# pc-gen-breadboard.net
KiCad netlist of a schematic drawn in EAGLE
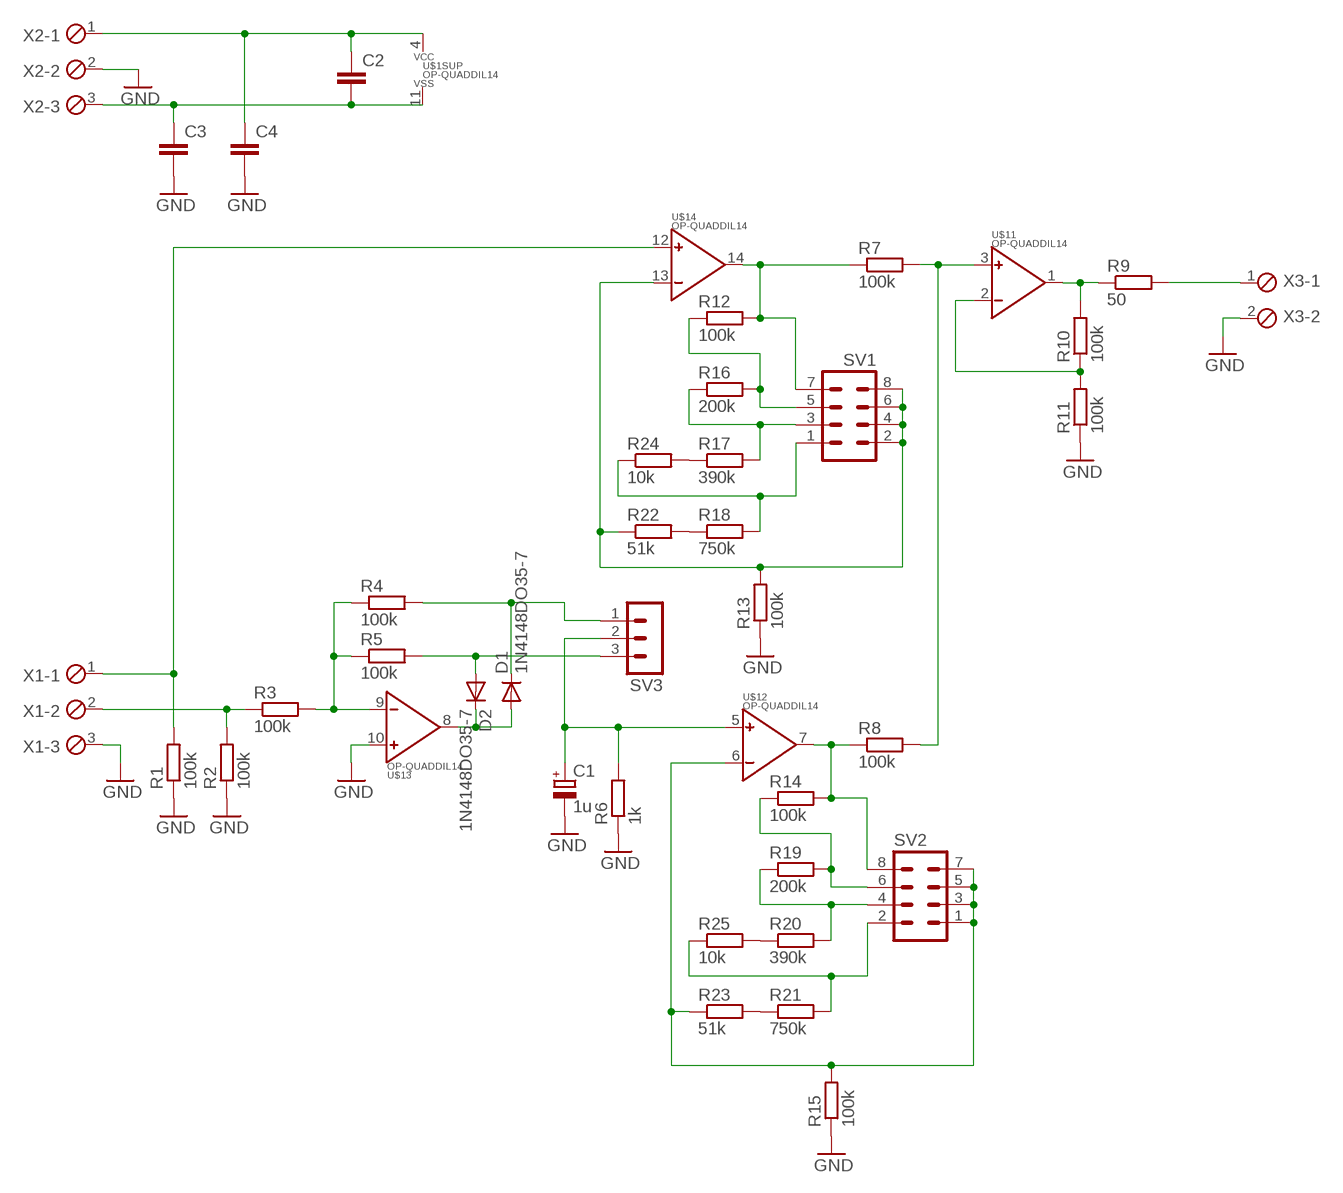
[diagram p0: schematic, sheet 1]

(export (version "E")
  (design (tool "Eeschema 10.0.6"))
  (components
    (comp (ref "C1")
      (value "1u")
      (footprint "eagle-import:E2,5-7")
      (libsource (lib "eagle-import") (part "CPOL-EUE2.5-7"))
    )
    (comp (ref "C2")
      (value "C-EU050-025X075")
      (footprint "eagle-import:C050-025X075")
      (libsource (lib "eagle-import") (part "C-EU050-025X075"))
    )
    (comp (ref "C3")
      (value "C-EU050-025X075")
      (footprint "eagle-import:C050-025X075")
      (libsource (lib "eagle-import") (part "C-EU050-025X075"))
    )
    (comp (ref "C4")
      (value "C-EU050-025X075")
      (footprint "eagle-import:C050-025X075")
      (libsource (lib "eagle-import") (part "C-EU050-025X075"))
    )
    (comp (ref "D1")
      (value "1N4148DO35-7")
      (footprint "eagle-import:DO35-7")
      (libsource (lib "eagle-import") (part "1N4148DO35-7"))
    )
    (comp (ref "D2")
      (value "1N4148DO35-7")
      (footprint "eagle-import:DO35-7")
      (libsource (lib "eagle-import") (part "1N4148DO35-7"))
    )
    (comp (ref "R1")
      (value "100k")
      (footprint "eagle-import:0207_2V")
      (libsource (lib "eagle-import") (part "R-EU_0207/2V"))
    )
    (comp (ref "R2")
      (value "100k")
      (footprint "eagle-import:0207_2V")
      (libsource (lib "eagle-import") (part "R-EU_0207/2V"))
    )
    (comp (ref "R3")
      (value "100k")
      (footprint "eagle-import:0207_7")
      (libsource (lib "eagle-import") (part "R-EU_0207/7"))
    )
    (comp (ref "R4")
      (value "100k")
      (footprint "eagle-import:0207_2V")
      (libsource (lib "eagle-import") (part "R-EU_0207/2V"))
    )
    (comp (ref "R5")
      (value "100k")
      (footprint "eagle-import:0207_2V")
      (libsource (lib "eagle-import") (part "R-EU_0207/2V"))
    )
    (comp (ref "R6")
      (value "1k")
      (footprint "eagle-import:0207_2V")
      (libsource (lib "eagle-import") (part "R-EU_0207/2V"))
    )
    (comp (ref "R7")
      (value "100k")
      (footprint "eagle-import:0207_7")
      (libsource (lib "eagle-import") (part "R-EU_0207/7"))
    )
    (comp (ref "R8")
      (value "100k")
      (footprint "eagle-import:0207_7")
      (libsource (lib "eagle-import") (part "R-EU_0207/7"))
    )
    (comp (ref "R9")
      (value "50")
      (footprint "eagle-import:0207_7")
      (libsource (lib "eagle-import") (part "R-EU_0207/7"))
    )
    (comp (ref "R10")
      (value "100k")
      (footprint "eagle-import:0207_2V")
      (libsource (lib "eagle-import") (part "R-EU_0207/2V"))
    )
    (comp (ref "R11")
      (value "100k")
      (footprint "eagle-import:0207_7")
      (libsource (lib "eagle-import") (part "R-EU_0207/7"))
    )
    (comp (ref "R12")
      (value "100k")
      (footprint "eagle-import:0207_2V")
      (libsource (lib "eagle-import") (part "R-EU_0207/2V"))
    )
    (comp (ref "R13")
      (value "100k")
      (footprint "eagle-import:0207_7")
      (libsource (lib "eagle-import") (part "R-EU_0207/7"))
    )
    (comp (ref "R14")
      (value "100k")
      (footprint "eagle-import:0207_2V")
      (libsource (lib "eagle-import") (part "R-EU_0207/2V"))
    )
    (comp (ref "R15")
      (value "100k")
      (footprint "eagle-import:0207_2V")
      (libsource (lib "eagle-import") (part "R-EU_0207/2V"))
    )
    (comp (ref "R16")
      (value "200k")
      (footprint "eagle-import:0207_2V")
      (libsource (lib "eagle-import") (part "R-EU_0207/2V"))
    )
    (comp (ref "R17")
      (value "390k")
      (footprint "eagle-import:0207_2V")
      (libsource (lib "eagle-import") (part "R-EU_0207/2V"))
    )
    (comp (ref "R18")
      (value "750k")
      (footprint "eagle-import:0207_2V")
      (libsource (lib "eagle-import") (part "R-EU_0207/2V"))
    )
    (comp (ref "R19")
      (value "200k")
      (footprint "eagle-import:0207_2V")
      (libsource (lib "eagle-import") (part "R-EU_0207/2V"))
    )
    (comp (ref "R20")
      (value "390k")
      (footprint "eagle-import:0207_2V")
      (libsource (lib "eagle-import") (part "R-EU_0207/2V"))
    )
    (comp (ref "R21")
      (value "750k")
      (footprint "eagle-import:0207_2V")
      (libsource (lib "eagle-import") (part "R-EU_0207/2V"))
    )
    (comp (ref "R22")
      (value "51k")
      (footprint "eagle-import:0207_2V")
      (libsource (lib "eagle-import") (part "R-EU_0207/2V"))
    )
    (comp (ref "R23")
      (value "51k")
      (footprint "eagle-import:0207_2V")
      (libsource (lib "eagle-import") (part "R-EU_0207/2V"))
    )
    (comp (ref "R24")
      (value "10k")
      (footprint "eagle-import:0207_2V")
      (libsource (lib "eagle-import") (part "R-EU_0207/2V"))
    )
    (comp (ref "R25")
      (value "10k")
      (footprint "eagle-import:0207_2V")
      (libsource (lib "eagle-import") (part "R-EU_0207/2V"))
    )
    (comp (ref "SV1")
      (value "MA04-2")
      (footprint "eagle-import:MA04-2")
      (libsource (lib "eagle-import") (part "MA04-2"))
    )
    (comp (ref "SV2")
      (value "MA04-2")
      (footprint "eagle-import:MA04-2")
      (libsource (lib "eagle-import") (part "MA04-2"))
    )
    (comp (ref "SV3")
      (value "MA03-1")
      (footprint "eagle-import:MA03-1")
      (libsource (lib "eagle-import") (part "MA03-1"))
    )
    (comp (ref "U$1")
      (value "OP-QUADDIL14")
      (footprint "eagle-import:DIL14")
      (libsource (lib "eagle-import") (part "OP-QUADDIL14"))
    )
    (comp (ref "X1")
      (value "MPT3")
      (footprint "eagle-import:3POL254")
      (libsource (lib "eagle-import") (part "MPT3"))
    )
    (comp (ref "X2")
      (value "MPT3")
      (footprint "eagle-import:3POL254")
      (libsource (lib "eagle-import") (part "MPT3"))
    )
    (comp (ref "X3")
      (value "MPT2")
      (footprint "eagle-import:2POL254")
      (libsource (lib "eagle-import") (part "MPT2"))
    )
  )
  (nets
    (net (code "1") (name "GND") (class "Default")
      (node (ref "C1") (pin "-") (pinfunction "-_-") (pintype "passive"))
      (node (ref "C3") (pin "2") (pinfunction "2_2") (pintype "passive"))
      (node (ref "C4") (pin "2") (pinfunction "2_2") (pintype "passive"))
      (node (ref "R1") (pin "1") (pinfunction "1_1") (pintype "passive"))
      (node (ref "R11") (pin "1") (pinfunction "1_1") (pintype "passive"))
      (node (ref "R13") (pin "1") (pinfunction "1_1") (pintype "passive"))
      (node (ref "R15") (pin "1") (pinfunction "1_1") (pintype "passive"))
      (node (ref "R2") (pin "1") (pinfunction "1_1") (pintype "passive"))
      (node (ref "R6") (pin "1") (pinfunction "1_1") (pintype "passive"))
      (node (ref "U$1") (pin "10") (pinfunction "POS_10") (pintype "bidirectional"))
      (node (ref "X1") (pin "3") (pinfunction "1_3") (pintype "passive"))
      (node (ref "X2") (pin "2") (pinfunction "1_2") (pintype "passive"))
      (node (ref "X3") (pin "2") (pinfunction "1_2") (pintype "passive"))
    )
    (net (code "2") (name "Net-(D1-PadC)") (class "Default")
      (node (ref "D1") (pin "C") (pinfunction "C_C") (pintype "passive"))
      (node (ref "R4") (pin "2") (pinfunction "2_2") (pintype "passive"))
      (node (ref "SV3") (pin "1") (pinfunction "1_1") (pintype "passive"))
    )
    (net (code "3") (name "Net-(D2-PadA)") (class "Default")
      (node (ref "D2") (pin "A") (pinfunction "A_A") (pintype "passive"))
      (node (ref "R5") (pin "2") (pinfunction "2_2") (pintype "passive"))
      (node (ref "SV3") (pin "3") (pinfunction "3_3") (pintype "passive"))
    )
    (net (code "4") (name "Net-(R9-Pad2)") (class "Default")
      (node (ref "R9") (pin "2") (pinfunction "2_2") (pintype "passive"))
      (node (ref "X3") (pin "1") (pinfunction "1_1") (pintype "passive"))
    )
    (net (code "5") (name "Net-(R12-Pad1)") (class "Default")
      (node (ref "R12") (pin "1") (pinfunction "1_1") (pintype "passive"))
      (node (ref "R16") (pin "2") (pinfunction "2_2") (pintype "passive"))
      (node (ref "SV1") (pin "5") (pinfunction "5_5") (pintype "passive"))
    )
    (net (code "6") (name "Net-(R14-Pad1)") (class "Default")
      (node (ref "R14") (pin "1") (pinfunction "1_1") (pintype "passive"))
      (node (ref "R19") (pin "2") (pinfunction "2_2") (pintype "passive"))
      (node (ref "SV2") (pin "6") (pinfunction "6_6") (pintype "passive"))
    )
    (net (code "7") (name "Net-(R16-Pad1)") (class "Default")
      (node (ref "R16") (pin "1") (pinfunction "1_1") (pintype "passive"))
      (node (ref "R17") (pin "2") (pinfunction "2_2") (pintype "passive"))
      (node (ref "SV1") (pin "3") (pinfunction "3_3") (pintype "passive"))
    )
    (net (code "8") (name "Net-(R17-Pad1)") (class "Default")
      (node (ref "R17") (pin "1") (pinfunction "1_1") (pintype "passive"))
      (node (ref "R24") (pin "2") (pinfunction "2_2") (pintype "passive"))
    )
    (net (code "9") (name "Net-(R18-Pad1)") (class "Default")
      (node (ref "R18") (pin "1") (pinfunction "1_1") (pintype "passive"))
      (node (ref "R22") (pin "2") (pinfunction "2_2") (pintype "passive"))
    )
    (net (code "10") (name "Net-(R18-Pad2)") (class "Default")
      (node (ref "R18") (pin "2") (pinfunction "2_2") (pintype "passive"))
      (node (ref "R24") (pin "1") (pinfunction "1_1") (pintype "passive"))
      (node (ref "SV1") (pin "1") (pinfunction "1_1") (pintype "passive"))
    )
    (net (code "11") (name "Net-(R19-Pad1)") (class "Default")
      (node (ref "R19") (pin "1") (pinfunction "1_1") (pintype "passive"))
      (node (ref "R20") (pin "2") (pinfunction "2_2") (pintype "passive"))
      (node (ref "SV2") (pin "4") (pinfunction "4_4") (pintype "passive"))
    )
    (net (code "12") (name "Net-(R20-Pad1)") (class "Default")
      (node (ref "R20") (pin "1") (pinfunction "1_1") (pintype "passive"))
      (node (ref "R25") (pin "2") (pinfunction "2_2") (pintype "passive"))
    )
    (net (code "13") (name "Net-(R21-Pad1)") (class "Default")
      (node (ref "R21") (pin "1") (pinfunction "1_1") (pintype "passive"))
      (node (ref "R23") (pin "2") (pinfunction "2_2") (pintype "passive"))
    )
    (net (code "14") (name "Net-(R21-Pad2)") (class "Default")
      (node (ref "R21") (pin "2") (pinfunction "2_2") (pintype "passive"))
      (node (ref "R25") (pin "1") (pinfunction "1_1") (pintype "passive"))
      (node (ref "SV2") (pin "2") (pinfunction "2_2") (pintype "passive"))
    )
    (net (code "15") (name "Net-(U$1A-NEG)") (class "Default")
      (node (ref "R10") (pin "1") (pinfunction "1_1") (pintype "passive"))
      (node (ref "R11") (pin "2") (pinfunction "2_2") (pintype "passive"))
      (node (ref "U$1") (pin "2") (pinfunction "NEG_2") (pintype "bidirectional"))
    )
    (net (code "16") (name "Net-(U$1A-OUT)") (class "Default")
      (node (ref "R10") (pin "2") (pinfunction "2_2") (pintype "passive"))
      (node (ref "R9") (pin "1") (pinfunction "1_1") (pintype "passive"))
      (node (ref "U$1") (pin "1") (pinfunction "OUT_1") (pintype "bidirectional"))
    )
    (net (code "17") (name "Net-(U$1A-POS)") (class "Default")
      (node (ref "R7") (pin "2") (pinfunction "2_2") (pintype "passive"))
      (node (ref "R8") (pin "2") (pinfunction "2_2") (pintype "passive"))
      (node (ref "U$1") (pin "3") (pinfunction "POS_3") (pintype "bidirectional"))
    )
    (net (code "18") (name "Net-(U$1B-NEG)") (class "Default")
      (node (ref "R15") (pin "2") (pinfunction "2_2") (pintype "passive"))
      (node (ref "R23") (pin "1") (pinfunction "1_1") (pintype "passive"))
      (node (ref "SV2") (pin "1") (pinfunction "1_1") (pintype "passive"))
      (node (ref "SV2") (pin "3") (pinfunction "3_3") (pintype "passive"))
      (node (ref "SV2") (pin "5") (pinfunction "5_5") (pintype "passive"))
      (node (ref "SV2") (pin "7") (pinfunction "7_7") (pintype "passive"))
      (node (ref "U$1") (pin "6") (pinfunction "NEG_6") (pintype "bidirectional"))
    )
    (net (code "19") (name "Net-(U$1B-OUT)") (class "Default")
      (node (ref "R14") (pin "2") (pinfunction "2_2") (pintype "passive"))
      (node (ref "R8") (pin "1") (pinfunction "1_1") (pintype "passive"))
      (node (ref "SV2") (pin "8") (pinfunction "8_8") (pintype "passive"))
      (node (ref "U$1") (pin "7") (pinfunction "OUT_7") (pintype "bidirectional"))
    )
    (net (code "20") (name "Net-(U$1B-POS)") (class "Default")
      (node (ref "C1") (pin "+") (pinfunction "+_+") (pintype "passive"))
      (node (ref "R6") (pin "2") (pinfunction "2_2") (pintype "passive"))
      (node (ref "SV3") (pin "2") (pinfunction "2_2") (pintype "passive"))
      (node (ref "U$1") (pin "5") (pinfunction "POS_5") (pintype "bidirectional"))
    )
    (net (code "21") (name "Net-(U$1C-NEG)") (class "Default")
      (node (ref "R3") (pin "2") (pinfunction "2_2") (pintype "passive"))
      (node (ref "R4") (pin "1") (pinfunction "1_1") (pintype "passive"))
      (node (ref "R5") (pin "1") (pinfunction "1_1") (pintype "passive"))
      (node (ref "U$1") (pin "9") (pinfunction "NEG_9") (pintype "bidirectional"))
    )
    (net (code "22") (name "Net-(U$1C-OUT)") (class "Default")
      (node (ref "D1") (pin "A") (pinfunction "A_A") (pintype "passive"))
      (node (ref "D2") (pin "C") (pinfunction "C_C") (pintype "passive"))
      (node (ref "U$1") (pin "8") (pinfunction "OUT_8") (pintype "bidirectional"))
    )
    (net (code "23") (name "Net-(U$1D-NEG)") (class "Default")
      (node (ref "R13") (pin "2") (pinfunction "2_2") (pintype "passive"))
      (node (ref "R22") (pin "1") (pinfunction "1_1") (pintype "passive"))
      (node (ref "SV1") (pin "2") (pinfunction "2_2") (pintype "passive"))
      (node (ref "SV1") (pin "4") (pinfunction "4_4") (pintype "passive"))
      (node (ref "SV1") (pin "6") (pinfunction "6_6") (pintype "passive"))
      (node (ref "SV1") (pin "8") (pinfunction "8_8") (pintype "passive"))
      (node (ref "U$1") (pin "13") (pinfunction "NEG_13") (pintype "bidirectional"))
    )
    (net (code "24") (name "Net-(U$1D-OUT)") (class "Default")
      (node (ref "R12") (pin "2") (pinfunction "2_2") (pintype "passive"))
      (node (ref "R7") (pin "1") (pinfunction "1_1") (pintype "passive"))
      (node (ref "SV1") (pin "7") (pinfunction "7_7") (pintype "passive"))
      (node (ref "U$1") (pin "14") (pinfunction "OUT_14") (pintype "bidirectional"))
    )
    (net (code "25") (name "Net-(U$1D-POS)") (class "Default")
      (node (ref "R1") (pin "2") (pinfunction "2_2") (pintype "passive"))
      (node (ref "U$1") (pin "12") (pinfunction "POS_12") (pintype "bidirectional"))
      (node (ref "X1") (pin "1") (pinfunction "1_1") (pintype "passive"))
    )
    (net (code "26") (name "Net-(U$1E-VCC)") (class "Default")
      (node (ref "C2") (pin "1") (pinfunction "1_1") (pintype "passive"))
      (node (ref "C4") (pin "1") (pinfunction "1_1") (pintype "passive"))
      (node (ref "U$1") (pin "4") (pinfunction "VCC_4") (pintype "bidirectional"))
      (node (ref "X2") (pin "1") (pinfunction "1_1") (pintype "passive"))
    )
    (net (code "27") (name "Net-(U$1E-VSS)") (class "Default")
      (node (ref "C2") (pin "2") (pinfunction "2_2") (pintype "passive"))
      (node (ref "C3") (pin "1") (pinfunction "1_1") (pintype "passive"))
      (node (ref "U$1") (pin "11") (pinfunction "VSS_11") (pintype "bidirectional"))
      (node (ref "X2") (pin "3") (pinfunction "1_3") (pintype "passive"))
    )
    (net (code "28") (name "Net-(X1B-1)") (class "Default")
      (node (ref "R2") (pin "2") (pinfunction "2_2") (pintype "passive"))
      (node (ref "R3") (pin "1") (pinfunction "1_1") (pintype "passive"))
      (node (ref "X1") (pin "2") (pinfunction "1_2") (pintype "passive"))
    )
  )
)
